# Part22_ETH_WAN.net
KiCad netlist of a schematic drawn in Altium Designer
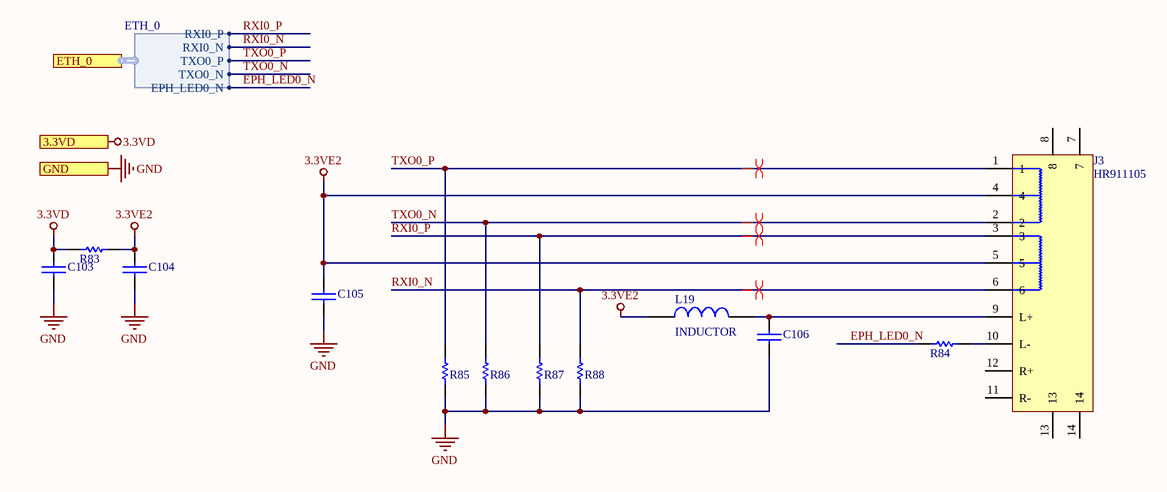
[diagram p0: Part22_ETH_WAN.SchDoc]

(export (version "E")
  (design (tool "Eeschema 10.0.6"))
  (components
    (comp (ref "C103")
      (value "100nF")
      (footprint "0402C")
      (description "无极性电容")
      (libsource (lib "电容") (part "CAP"))
    )
    (comp (ref "C104")
      (value "100nF")
      (footprint "0402C")
      (description "无极性电容")
      (libsource (lib "电容") (part "CAP"))
    )
    (comp (ref "C105")
      (value "100nF")
      (footprint "0402C")
      (description "无极性电容")
      (libsource (lib "电容") (part "CAP"))
    )
    (comp (ref "C106")
      (value "100nF")
      (footprint "0402C")
      (description "无极性电容")
      (libsource (lib "电容") (part "CAP"))
    )
    (comp (ref "J3") (value "HR911105") (footprint "HR911105A") (libsource (lib "网络插座") (part "HR911105")))
    (comp (ref "L19") (value "INDUCTOR") (footprint "0402L") (libsource (lib "电感") (part "INDUCTOR")))
    (comp (ref "R83") (value "0R") (footprint "0402R") (libsource (lib "电阻") (part "RES")))
    (comp (ref "R84") (value "1K") (footprint "0402R") (libsource (lib "电阻") (part "RES")))
    (comp (ref "R85") (value "49.9R") (footprint "0402R") (libsource (lib "电阻") (part "RES")))
    (comp (ref "R86") (value "49.9R") (footprint "0402R") (libsource (lib "电阻") (part "RES")))
    (comp (ref "R87") (value "49.9R") (footprint "0402R") (libsource (lib "电阻") (part "RES")))
    (comp (ref "R88") (value "49.9R") (footprint "0402R") (libsource (lib "电阻") (part "RES")))
  )
  (nets
    (net (code "2") (name "/EPH_LED0_N") (class "Default")
      (node (ref "R84") (pin "2") (pinfunction "2_2") (pintype "passive"))
    )
    (net (code "3") (name "/RXI0_N") (class "Default")
      (node (ref "J3") (pin "6") (pinfunction "6_6") (pintype "passive"))
      (node (ref "R88") (pin "2") (pinfunction "2_2") (pintype "passive"))
    )
    (net (code "4") (name "/RXI0_P") (class "Default")
      (node (ref "J3") (pin "3") (pinfunction "3_3") (pintype "passive"))
      (node (ref "R87") (pin "2") (pinfunction "2_2") (pintype "passive"))
    )
    (net (code "5") (name "/TXO0_N") (class "Default")
      (node (ref "J3") (pin "2") (pinfunction "2_2") (pintype "passive"))
      (node (ref "R86") (pin "2") (pinfunction "2_2") (pintype "passive"))
    )
    (net (code "6") (name "/TXO0_P") (class "Default")
      (node (ref "J3") (pin "1") (pinfunction "1_1") (pintype "passive"))
      (node (ref "R85") (pin "2") (pinfunction "2_2") (pintype "passive"))
    )
    (net (code "8") (name "3.3VD") (class "Default")
      (node (ref "C103") (pin "1") (pinfunction "1_1") (pintype "passive"))
      (node (ref "R83") (pin "1") (pinfunction "1_1") (pintype "passive"))
    )
    (net (code "9") (name "3.3VE2") (class "Default")
      (node (ref "C104") (pin "1") (pinfunction "1_1") (pintype "passive"))
      (node (ref "C105") (pin "1") (pinfunction "1_1") (pintype "passive"))
      (node (ref "J3") (pin "4") (pinfunction "4_4") (pintype "passive"))
      (node (ref "J3") (pin "5") (pinfunction "5_5") (pintype "passive"))
      (node (ref "L19") (pin "1") (pinfunction "1_1") (pintype "passive"))
      (node (ref "R83") (pin "2") (pinfunction "2_2") (pintype "passive"))
    )
    (net (code "10") (name "GND") (class "Default")
      (node (ref "C103") (pin "2") (pinfunction "2_2") (pintype "passive"))
      (node (ref "C104") (pin "2") (pinfunction "2_2") (pintype "passive"))
      (node (ref "C105") (pin "2") (pinfunction "2_2") (pintype "passive"))
      (node (ref "C106") (pin "2") (pinfunction "2_2") (pintype "passive"))
      (node (ref "R85") (pin "1") (pinfunction "1_1") (pintype "passive"))
      (node (ref "R86") (pin "1") (pinfunction "1_1") (pintype "passive"))
      (node (ref "R87") (pin "1") (pinfunction "1_1") (pintype "passive"))
      (node (ref "R88") (pin "1") (pinfunction "1_1") (pintype "passive"))
    )
    (net (code "11") (name "Net-(J3-L+)") (class "Default")
      (node (ref "C106") (pin "1") (pinfunction "1_1") (pintype "passive"))
      (node (ref "J3") (pin "9") (pinfunction "L+_9") (pintype "passive"))
      (node (ref "L19") (pin "2") (pinfunction "2_2") (pintype "passive"))
    )
    (net (code "12") (name "Net-(J3-L-)") (class "Default")
      (node (ref "J3") (pin "10") (pinfunction "L-_10") (pintype "passive"))
      (node (ref "R84") (pin "1") (pinfunction "1_1") (pintype "passive"))
    )
    (net (code "13") (name "unconnected-(J3-Pad7)") (class "Default")
      (node (ref "J3") (pin "7") (pinfunction "7_7") (pintype "passive"))
    )
    (net (code "14") (name "unconnected-(J3-Pad8)") (class "Default")
      (node (ref "J3") (pin "8") (pinfunction "8_8") (pintype "passive"))
    )
    (net (code "15") (name "unconnected-(J3-Pad13)") (class "Default")
      (node (ref "J3") (pin "13") (pinfunction "13_13") (pintype "passive"))
    )
    (net (code "16") (name "unconnected-(J3-Pad14)") (class "Default")
      (node (ref "J3") (pin "14") (pinfunction "14_14") (pintype "passive"))
    )
    (net (code "17") (name "unconnected-(J3-R+-Pad12)") (class "Default")
      (node (ref "J3") (pin "12") (pinfunction "R+_12") (pintype "passive"))
    )
    (net (code "18") (name "unconnected-(J3-R--Pad11)") (class "Default")
      (node (ref "J3") (pin "11") (pinfunction "R-_11") (pintype "passive"))
    )
  )
)
